# SparkFun_FreeSoC2_V1.net
KiCad netlist of a schematic drawn in EAGLE
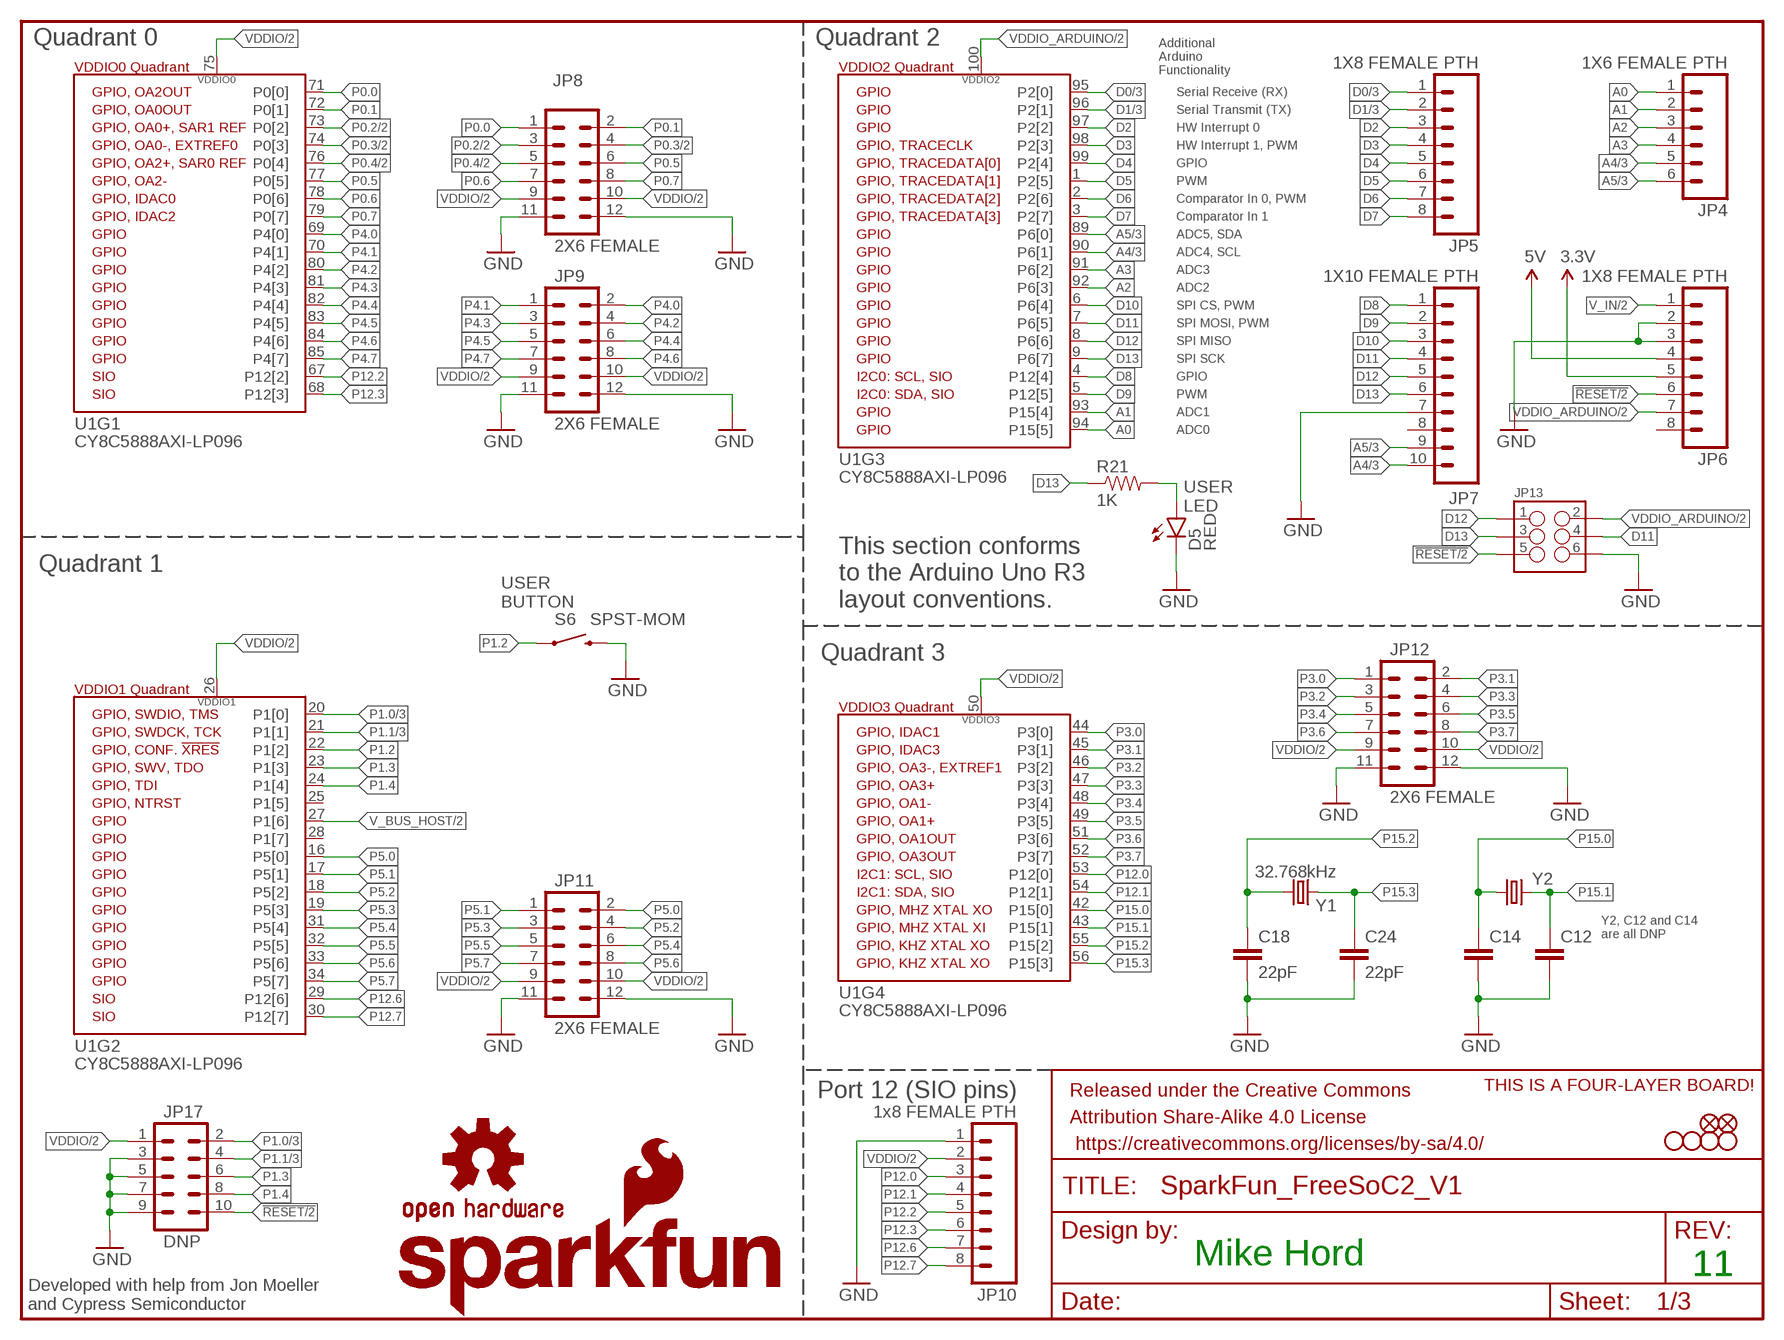
[diagram p0: schematic, sheet 1]
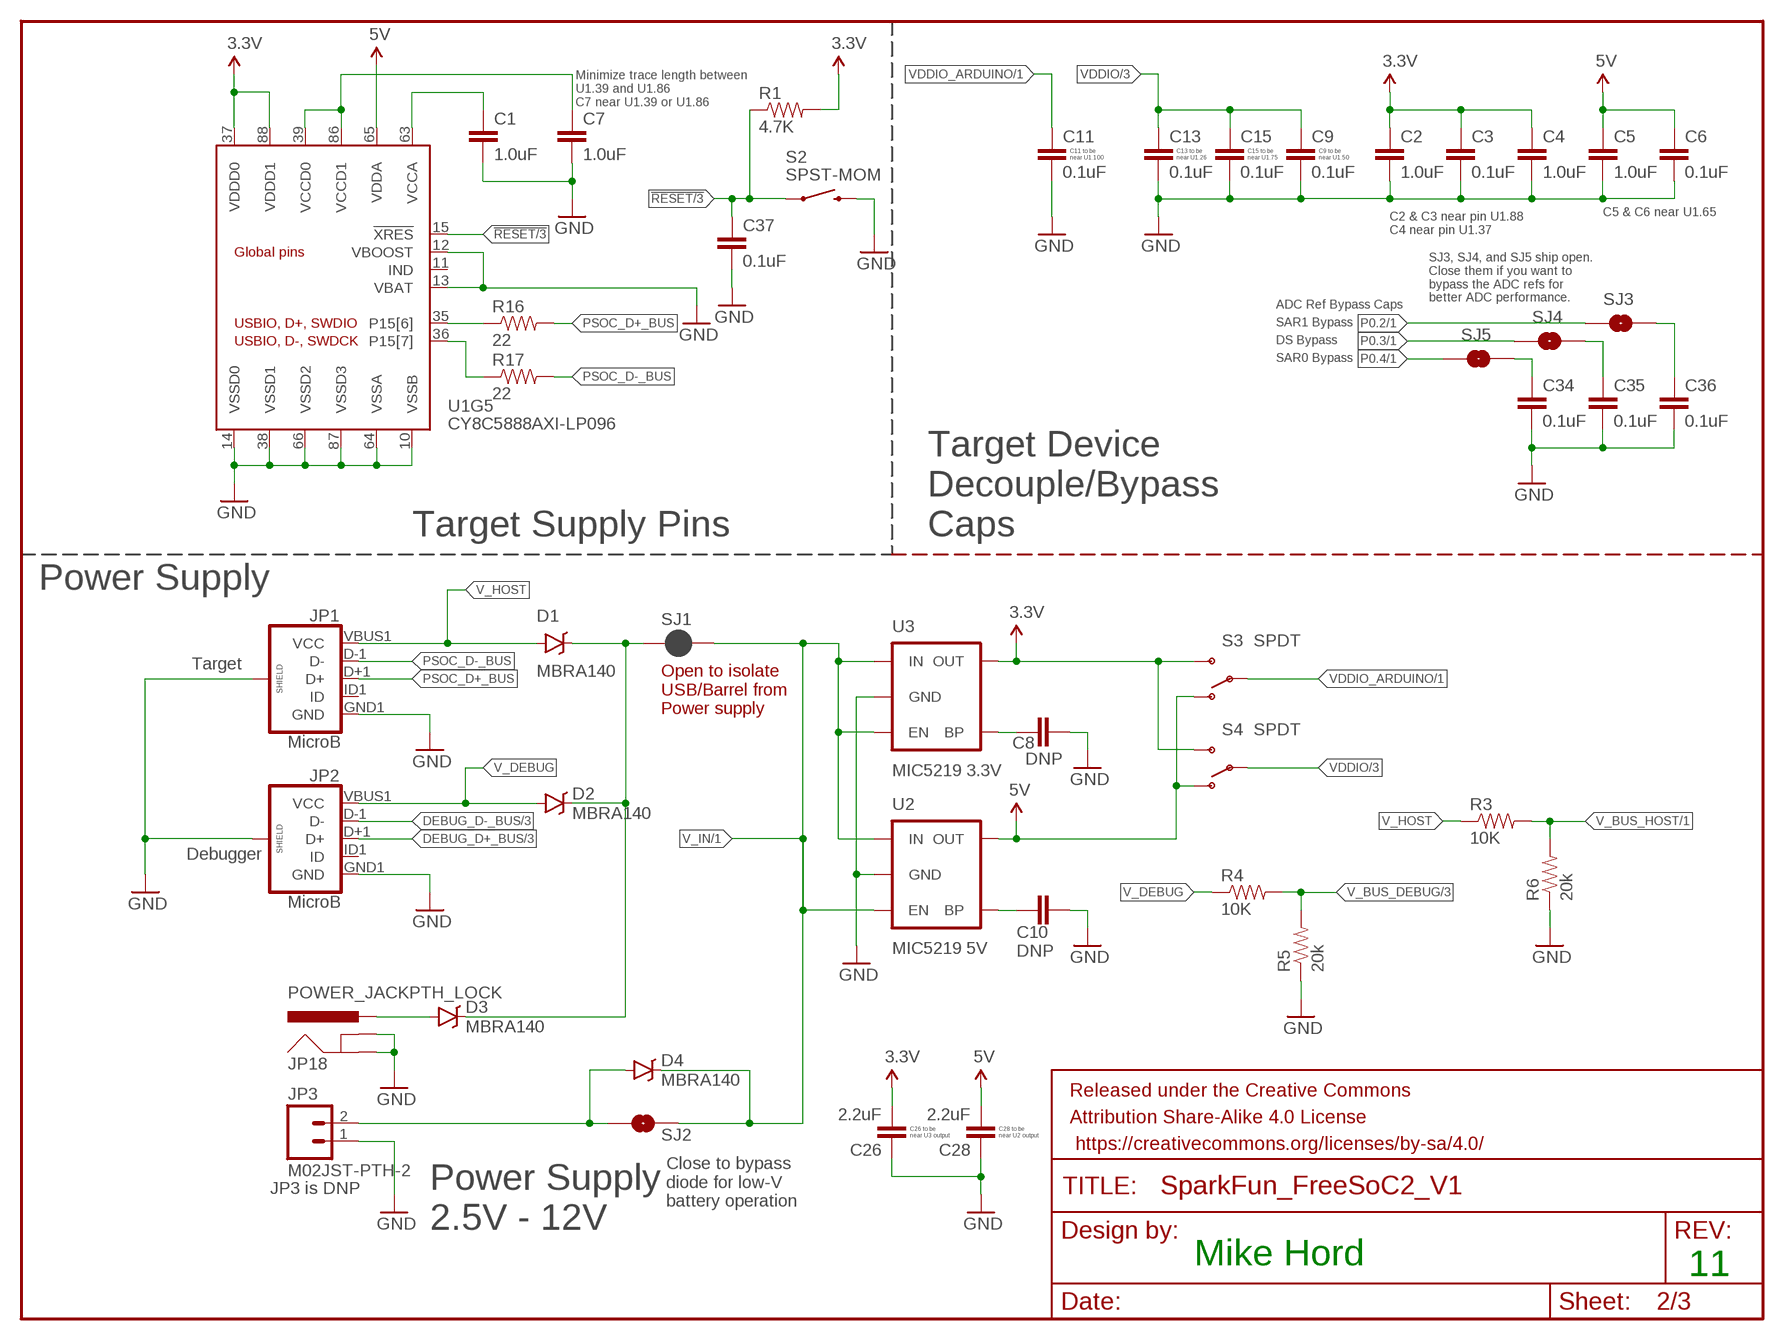
[diagram p1: schematic, sheet 2]
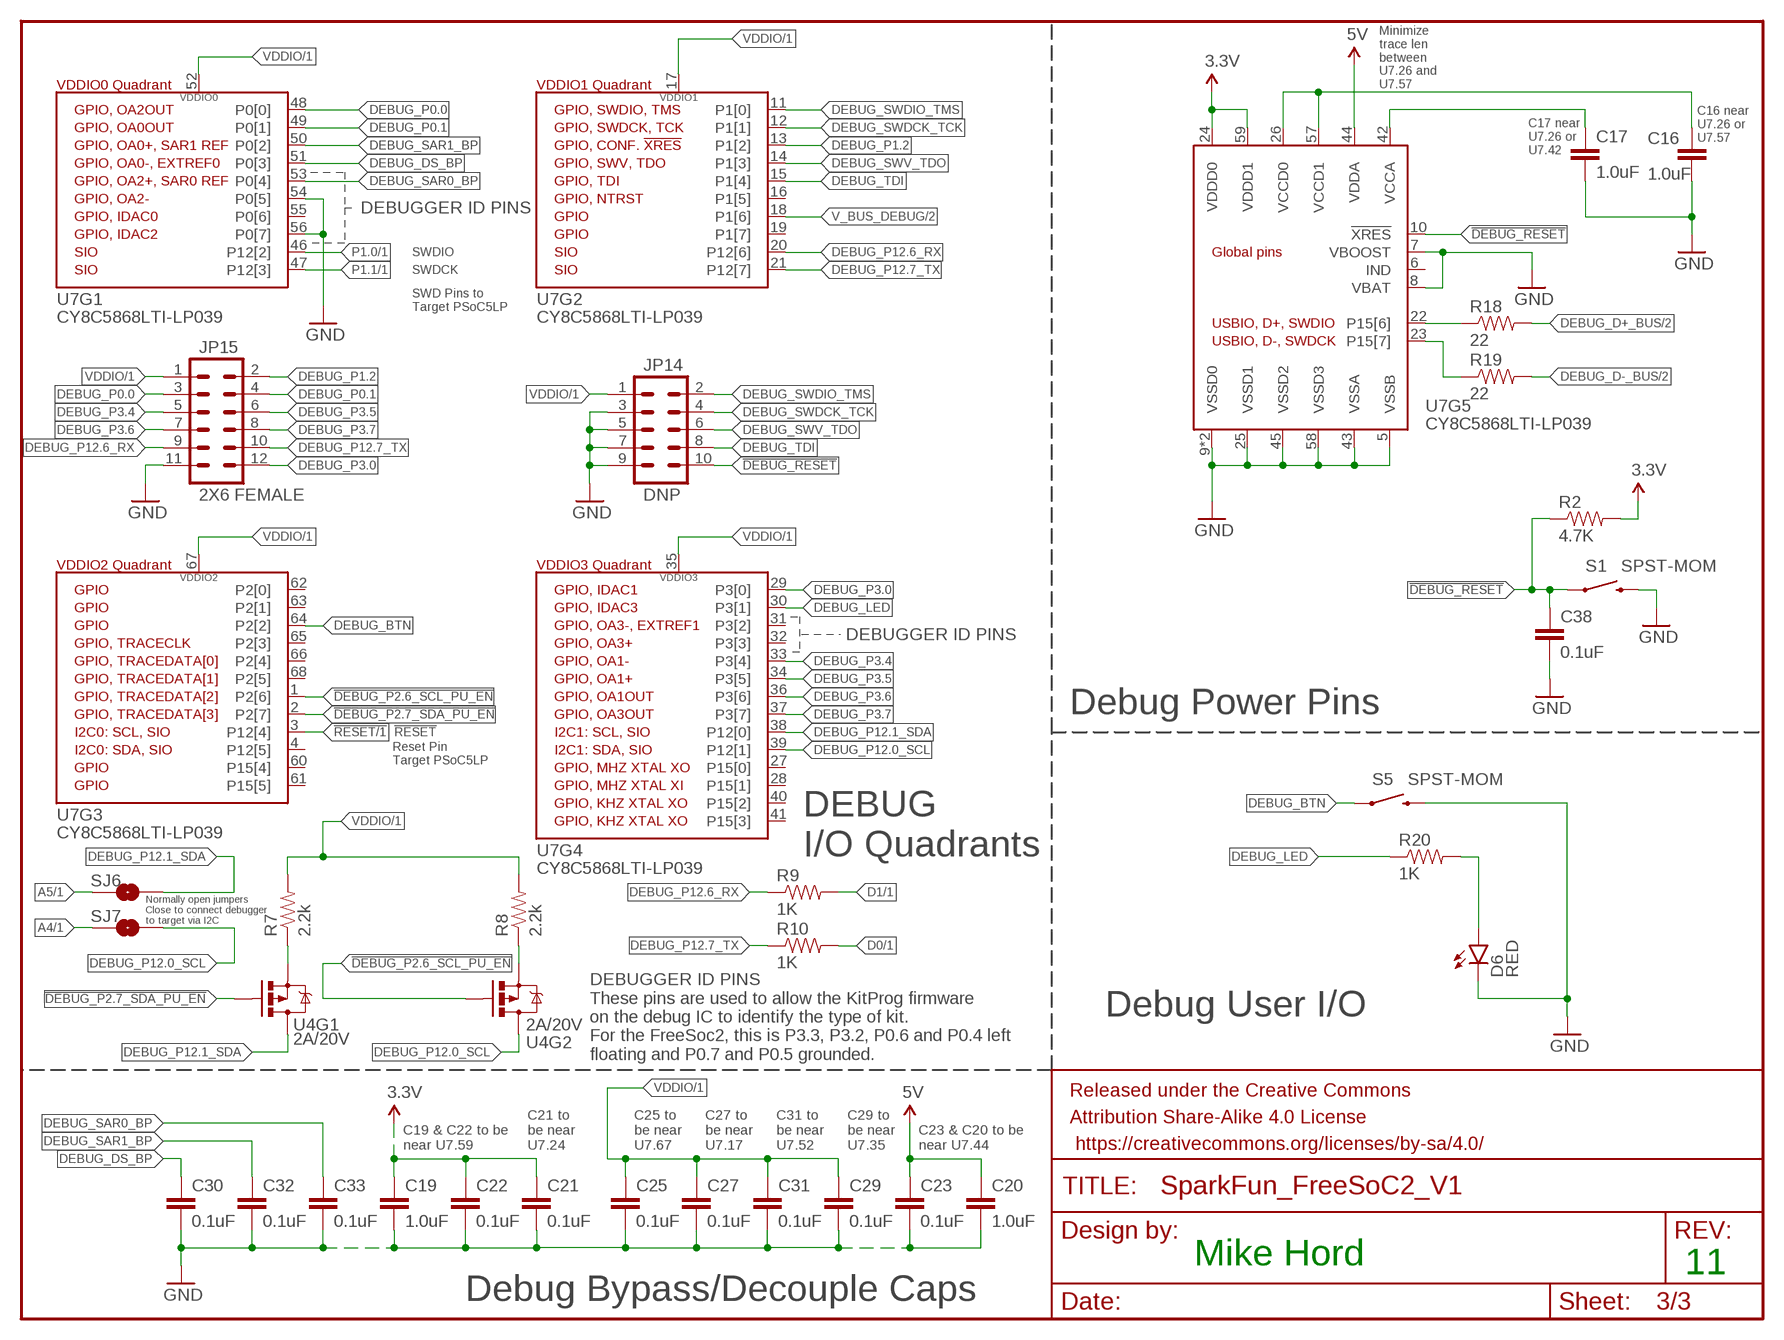
[diagram p2: schematic, sheet 3]

(export (version "E")
  (design (tool "Eeschema 10.0.6"))
  (components
    (comp (ref "C1")
      (value "1.0uF")
      (footprint "eagle-import:0402-CAP")
      (libsource (lib "eagle-import") (part "1.0UF-16V-10%(0402)"))
    )
    (comp (ref "C2")
      (value "1.0uF")
      (footprint "eagle-import:0402-CAP")
      (libsource (lib "eagle-import") (part "1.0UF-16V-10%(0402)"))
    )
    (comp (ref "C3")
      (value "0.1uF")
      (footprint "eagle-import:0402-CAP")
      (libsource (lib "eagle-import") (part "0.1UF-16V(+-10%)(0402)"))
    )
    (comp (ref "C4")
      (value "1.0uF")
      (footprint "eagle-import:0402-CAP")
      (libsource (lib "eagle-import") (part "1.0UF-16V-10%(0402)"))
    )
    (comp (ref "C5")
      (value "1.0uF")
      (footprint "eagle-import:0402-CAP")
      (libsource (lib "eagle-import") (part "1.0UF-16V-10%(0402)"))
    )
    (comp (ref "C6")
      (value "0.1uF")
      (footprint "eagle-import:0402-CAP")
      (libsource (lib "eagle-import") (part "0.1UF-16V(+-10%)(0402)"))
    )
    (comp (ref "C7")
      (value "1.0uF")
      (footprint "eagle-import:0402-CAP")
      (libsource (lib "eagle-import") (part "1.0UF-16V-10%(0402)"))
    )
    (comp (ref "C8")
      (value "DNP")
      (footprint "eagle-import:0603-CAP")
      (libsource (lib "eagle-import") (part "470PF-50V-5%(0603)SMD"))
    )
    (comp (ref "C9")
      (value "0.1uF")
      (footprint "eagle-import:0402-CAP")
      (libsource (lib "eagle-import") (part "0.1UF-16V(+-10%)(0402)"))
    )
    (comp (ref "C10")
      (value "DNP")
      (footprint "eagle-import:0603-CAP")
      (libsource (lib "eagle-import") (part "470PF-50V-5%(0603)SMD"))
    )
    (comp (ref "C11")
      (value "0.1uF")
      (footprint "eagle-import:0402-CAP")
      (libsource (lib "eagle-import") (part "0.1UF-16V(+-10%)(0402)"))
    )
    (comp (ref "C13")
      (value "0.1uF")
      (footprint "eagle-import:0402-CAP")
      (libsource (lib "eagle-import") (part "0.1UF-16V(+-10%)(0402)"))
    )
    (comp (ref "C15")
      (value "0.1uF")
      (footprint "eagle-import:0402-CAP")
      (libsource (lib "eagle-import") (part "0.1UF-16V(+-10%)(0402)"))
    )
    (comp (ref "C26")
      (value "2.2uF")
      (footprint "eagle-import:0603-CAP")
      (libsource (lib "eagle-import") (part "2.2UF-10V-20%(0603)"))
    )
    (comp (ref "C28")
      (value "2.2uF")
      (footprint "eagle-import:0603-CAP")
      (libsource (lib "eagle-import") (part "2.2UF-10V-20%(0603)"))
    )
    (comp (ref "C34")
      (value "0.1uF")
      (footprint "eagle-import:0402-CAP")
      (libsource (lib "eagle-import") (part "0.1UF-16V(+-10%)(0402)"))
    )
    (comp (ref "C35")
      (value "0.1uF")
      (footprint "eagle-import:0402-CAP")
      (libsource (lib "eagle-import") (part "0.1UF-16V(+-10%)(0402)"))
    )
    (comp (ref "C36")
      (value "0.1uF")
      (footprint "eagle-import:0402-CAP")
      (libsource (lib "eagle-import") (part "0.1UF-16V(+-10%)(0402)"))
    )
    (comp (ref "C37")
      (value "0.1uF")
      (footprint "eagle-import:0402-CAP")
      (libsource (lib "eagle-import") (part "0.1UF-16V(+-10%)(0402)"))
    )
    (comp (ref "D1")
      (value "MBRA140")
      (footprint "eagle-import:SMA-DIODE")
      (libsource (lib "eagle-import") (part "MBRA140"))
    )
    (comp (ref "D2")
      (value "MBRA140")
      (footprint "eagle-import:SMA-DIODE")
      (libsource (lib "eagle-import") (part "MBRA140"))
    )
    (comp (ref "D3")
      (value "MBRA140")
      (footprint "eagle-import:SMA-DIODE")
      (libsource (lib "eagle-import") (part "MBRA140"))
    )
    (comp (ref "D4")
      (value "MBRA140")
      (footprint "eagle-import:SMA-DIODE")
      (libsource (lib "eagle-import") (part "MBRA140"))
    )
    (comp (ref "FRAME2")
      (value "FRAME-LETTERNO_PACKAGE")
      (footprint "eagle-import:DUMMY")
      (fields (field (name "DESIGNER") "Nobody"))
      (libsource (lib "eagle-import") (part "FRAME-LETTERNO_PACKAGE"))
    )
    (comp (ref "JP1")
      (value "MicroB")
      (footprint "eagle-import:USB-B-MICRO-SMD_V03")
      (libsource (lib "eagle-import") (part "USB_MICROB_PLUGCONN-11752"))
    )
    (comp (ref "JP2")
      (value "MicroB")
      (footprint "eagle-import:USB-B-MICRO-SMD_V03")
      (libsource (lib "eagle-import") (part "USB_MICROB_PLUGCONN-11752"))
    )
    (comp (ref "JP3")
      (value "M02JST-PTH-2")
      (footprint "eagle-import:JST-2-PTH")
      (libsource (lib "eagle-import") (part "M02JST-PTH-2"))
    )
    (comp (ref "JP18")
      (value "POWER_JACKPTH_LOCK")
      (footprint "eagle-import:POWER_JACK_PTH_LOCK")
      (libsource (lib "eagle-import") (part "POWER_JACKPTH_LOCK"))
    )
    (comp (ref "R1")
      (value "4.7K")
      (footprint "eagle-import:0603-RES")
      (libsource (lib "eagle-import") (part "4.7KOHM-1/10W-1%(0603)"))
    )
    (comp (ref "R3")
      (value "10K")
      (footprint "eagle-import:0603-RES")
      (libsource (lib "eagle-import") (part "10KOHM-1/10W-1%(0603)0603"))
    )
    (comp (ref "R4")
      (value "10K")
      (footprint "eagle-import:0603-RES")
      (libsource (lib "eagle-import") (part "10KOHM-1/10W-1%(0603)0603"))
    )
    (comp (ref "R5")
      (value "20k")
      (footprint "eagle-import:0603-RES")
      (libsource (lib "eagle-import") (part "20KOHM1/10W1%(0603)"))
    )
    (comp (ref "R6")
      (value "20k")
      (footprint "eagle-import:0603-RES")
      (libsource (lib "eagle-import") (part "20KOHM1/10W1%(0603)"))
    )
    (comp (ref "R16")
      (value "22")
      (footprint "eagle-import:0402-RES")
      (libsource (lib "eagle-import") (part "22OHM1/10W1%(0402)"))
    )
    (comp (ref "R17")
      (value "22")
      (footprint "eagle-import:0402-RES")
      (libsource (lib "eagle-import") (part "22OHM1/10W1%(0402)"))
    )
    (comp (ref "S2")
      (value "SPST-MOM")
      (footprint "eagle-import:TACTILE-SWITCH-SMD")
      (libsource (lib "eagle-import") (part "SWITCH-MOMENTARY-2SMD"))
    )
    (comp (ref "S3")
      (value "SPDT")
      (footprint "eagle-import:SWITCH-SPDT_LOCK.007S")
      (libsource (lib "eagle-import") (part "SWITCH-SPDTPTH_LOCK"))
    )
    (comp (ref "S4")
      (value "SPDT")
      (footprint "eagle-import:SWITCH-SPDT_LOCK.007S")
      (libsource (lib "eagle-import") (part "SWITCH-SPDTPTH_LOCK"))
    )
    (comp (ref "SJ1")
      (value "JUMPER-PAD-2-NC_BY_PASTE")
      (footprint "eagle-import:PAD-JUMPER-2-NC_BY_PASTE_YES_SILK")
      (libsource (lib "eagle-import") (part "JUMPER-PAD-2-NC_BY_PASTE"))
    )
    (comp (ref "SJ2")
      (value "JUMPER-PAD-2-NOYES_SILK")
      (footprint "eagle-import:PAD-JUMPER-2-NO_YES_SILK")
      (libsource (lib "eagle-import") (part "JUMPER-PAD-2-NOYES_SILK"))
    )
    (comp (ref "SJ3")
      (value "JUMPER-PAD-2-NO")
      (footprint "eagle-import:PAD-JUMPER-2-NO_NO_SILK")
      (libsource (lib "eagle-import") (part "JUMPER-PAD-2-NO"))
    )
    (comp (ref "SJ4")
      (value "JUMPER-PAD-2-NO")
      (footprint "eagle-import:PAD-JUMPER-2-NO_NO_SILK")
      (libsource (lib "eagle-import") (part "JUMPER-PAD-2-NO"))
    )
    (comp (ref "SJ5")
      (value "JUMPER-PAD-2-NO")
      (footprint "eagle-import:PAD-JUMPER-2-NO_NO_SILK")
      (libsource (lib "eagle-import") (part "JUMPER-PAD-2-NO"))
    )
    (comp (ref "U1")
      (value "CY8C5888AXI-LP096")
      (footprint "eagle-import:TQFP-100-14X14MM")
      (libsource (lib "eagle-import") (part "PSOC_5LP_100QFP"))
    )
    (comp (ref "U2")
      (value "MIC5219 5V")
      (footprint "eagle-import:SOT23-5")
      (libsource (lib "eagle-import") (part "V_REG_MIC52195V"))
    )
    (comp (ref "U3")
      (value "MIC5219 3.3V")
      (footprint "eagle-import:SOT23-5")
      (libsource (lib "eagle-import") (part "V_REG_MIC52193.3V"))
    )
    (comp (ref "C16")
      (value "1.0uF")
      (footprint "eagle-import:0402-CAP")
      (libsource (lib "eagle-import") (part "1.0UF-16V-10%(0402)"))
    )
    (comp (ref "C17")
      (value "1.0uF")
      (footprint "eagle-import:0402-CAP")
      (libsource (lib "eagle-import") (part "1.0UF-16V-10%(0402)"))
    )
    (comp (ref "C19")
      (value "1.0uF")
      (footprint "eagle-import:0402-CAP")
      (libsource (lib "eagle-import") (part "1.0UF-16V-10%(0402)"))
    )
    (comp (ref "C20")
      (value "1.0uF")
      (footprint "eagle-import:0402-CAP")
      (libsource (lib "eagle-import") (part "1.0UF-16V-10%(0402)"))
    )
    (comp (ref "C21")
      (value "0.1uF")
      (footprint "eagle-import:0402-CAP")
      (libsource (lib "eagle-import") (part "0.1UF-16V(+-10%)(0402)"))
    )
    (comp (ref "C22")
      (value "0.1uF")
      (footprint "eagle-import:0402-CAP")
      (libsource (lib "eagle-import") (part "0.1UF-16V(+-10%)(0402)"))
    )
    (comp (ref "C23")
      (value "0.1uF")
      (footprint "eagle-import:0402-CAP")
      (libsource (lib "eagle-import") (part "0.1UF-16V(+-10%)(0402)"))
    )
    (comp (ref "C25")
      (value "0.1uF")
      (footprint "eagle-import:0402-CAP")
      (libsource (lib "eagle-import") (part "0.1UF-16V(+-10%)(0402)"))
    )
    (comp (ref "C27")
      (value "0.1uF")
      (footprint "eagle-import:0402-CAP")
      (libsource (lib "eagle-import") (part "0.1UF-16V(+-10%)(0402)"))
    )
    (comp (ref "C29")
      (value "0.1uF")
      (footprint "eagle-import:0402-CAP")
      (libsource (lib "eagle-import") (part "0.1UF-16V(+-10%)(0402)"))
    )
    (comp (ref "C30")
      (value "0.1uF")
      (footprint "eagle-import:0402-CAP")
      (libsource (lib "eagle-import") (part "0.1UF-16V(+-10%)(0402)"))
    )
    (comp (ref "C31")
      (value "0.1uF")
      (footprint "eagle-import:0402-CAP")
      (libsource (lib "eagle-import") (part "0.1UF-16V(+-10%)(0402)"))
    )
    (comp (ref "C32")
      (value "0.1uF")
      (footprint "eagle-import:0402-CAP")
      (libsource (lib "eagle-import") (part "0.1UF-16V(+-10%)(0402)"))
    )
    (comp (ref "C33")
      (value "0.1uF")
      (footprint "eagle-import:0402-CAP")
      (libsource (lib "eagle-import") (part "0.1UF-16V(+-10%)(0402)"))
    )
    (comp (ref "C38")
      (value "0.1uF")
      (footprint "eagle-import:0402-CAP")
      (libsource (lib "eagle-import") (part "0.1UF-16V(+-10%)(0402)"))
    )
    (comp (ref "D6")
      (value "RED")
      (footprint "eagle-import:LED-0603")
      (libsource (lib "eagle-import") (part "LED-RED0603"))
    )
    (comp (ref "FRAME1")
      (value "FRAME-LETTERNO_PACKAGE")
      (footprint "eagle-import:DUMMY")
      (fields (field (name "DESIGNER") "Nobody"))
      (libsource (lib "eagle-import") (part "FRAME-LETTERNO_PACKAGE"))
    )
    (comp (ref "JP14")
      (value "DNP")
      (footprint "eagle-import:2X5_PTH_SILK_.05")
      (libsource (lib "eagle-import") (part "M05X20.05_IN_PTH_SILK"))
    )
    (comp (ref "JP15")
      (value "2X6 FEMALE")
      (footprint "eagle-import:2X6")
      (libsource (lib "eagle-import") (part "M06X2PTH_FEMALE"))
    )
    (comp (ref "R2")
      (value "4.7K")
      (footprint "eagle-import:0603-RES")
      (libsource (lib "eagle-import") (part "4.7KOHM-1/10W-1%(0603)"))
    )
    (comp (ref "R7")
      (value "2.2k")
      (footprint "eagle-import:0603-RES")
      (libsource (lib "eagle-import") (part "2.2KOHM-1/10W-1%(0603)"))
    )
    (comp (ref "R8")
      (value "2.2k")
      (footprint "eagle-import:0603-RES")
      (libsource (lib "eagle-import") (part "2.2KOHM-1/10W-1%(0603)"))
    )
    (comp (ref "R9")
      (value "1K")
      (footprint "eagle-import:0603-RES")
      (libsource (lib "eagle-import") (part "1KOHM1/10W1%(0603)"))
    )
    (comp (ref "R10")
      (value "1K")
      (footprint "eagle-import:0603-RES")
      (libsource (lib "eagle-import") (part "1KOHM1/10W1%(0603)"))
    )
    (comp (ref "R18")
      (value "22")
      (footprint "eagle-import:0402-RES")
      (libsource (lib "eagle-import") (part "22OHM1/10W1%(0402)"))
    )
    (comp (ref "R19")
      (value "22")
      (footprint "eagle-import:0402-RES")
      (libsource (lib "eagle-import") (part "22OHM1/10W1%(0402)"))
    )
    (comp (ref "R20")
      (value "1K")
      (footprint "eagle-import:0603-RES")
      (libsource (lib "eagle-import") (part "1KOHM1/10W1%(0603)"))
    )
    (comp (ref "S1")
      (value "SPST-MOM")
      (footprint "eagle-import:TACTILE-SWITCH-SMD")
      (libsource (lib "eagle-import") (part "SWITCH-MOMENTARY-2SMD"))
    )
    (comp (ref "S5")
      (value "SPST-MOM")
      (footprint "eagle-import:TACTILE-SWITCH-SMD")
      (libsource (lib "eagle-import") (part "SWITCH-MOMENTARY-2SMD"))
    )
    (comp (ref "SJ6")
      (value "JUMPER-PAD-2-NO")
      (footprint "eagle-import:PAD-JUMPER-2-NO_NO_SILK")
      (libsource (lib "eagle-import") (part "JUMPER-PAD-2-NO"))
    )
    (comp (ref "SJ7")
      (value "JUMPER-PAD-2-NO")
      (footprint "eagle-import:PAD-JUMPER-2-NO_NO_SILK")
      (libsource (lib "eagle-import") (part "JUMPER-PAD-2-NO"))
    )
    (comp (ref "U4")
      (value "2A/20V")
      (footprint "eagle-import:SOT26")
      (libsource (lib "eagle-import") (part "MOSFET-PCHANNEL_DUALSOT26"))
    )
    (comp (ref "U7")
      (value "CY8C5868LTI-LP039")
      (footprint "eagle-import:QFN-68")
      (libsource (lib "eagle-import") (part "PSOC_5LP_68QFN"))
    )
    (comp (ref "C12")
      (value "CAPPTH")
      (footprint "eagle-import:CAP-PTH-SMALL")
      (libsource (lib "eagle-import") (part "CAPPTH"))
    )
    (comp (ref "C14")
      (value "CAPPTH")
      (footprint "eagle-import:CAP-PTH-SMALL")
      (libsource (lib "eagle-import") (part "CAPPTH"))
    )
    (comp (ref "C18")
      (value "22pF")
      (footprint "eagle-import:0603-CAP")
      (libsource (lib "eagle-import") (part "22PF-50V-5%(0603)"))
    )
    (comp (ref "C24")
      (value "22pF")
      (footprint "eagle-import:0603-CAP")
      (libsource (lib "eagle-import") (part "22PF-50V-5%(0603)"))
    )
    (comp (ref "D5")
      (value "RED")
      (footprint "eagle-import:LED-0603")
      (libsource (lib "eagle-import") (part "LED-RED0603"))
    )
    (comp (ref "FID1")
      (value "FIDUCIAL1X2")
      (footprint "eagle-import:FIDUCIAL-1X2")
      (libsource (lib "eagle-import") (part "FIDUCIAL1X2"))
    )
    (comp (ref "FID2")
      (value "FIDUCIAL1X2")
      (footprint "eagle-import:FIDUCIAL-1X2")
      (libsource (lib "eagle-import") (part "FIDUCIAL1X2"))
    )
    (comp (ref "FRAME3")
      (value "FRAME-LETTERNO_PACKAGE")
      (footprint "eagle-import:DUMMY")
      (fields (field (name "DESIGNER") "Nobody"))
      (libsource (lib "eagle-import") (part "FRAME-LETTERNO_PACKAGE"))
    )
    (comp (ref "JP4")
      (value "1X6 FEMALE PTH")
      (footprint "eagle-import:1X06-SIP_LOCK")
      (libsource (lib "eagle-import") (part "M06SIP_LOCK"))
    )
    (comp (ref "JP5")
      (value "1X8 FEMALE PTH")
      (footprint "eagle-import:1X08_LOCK")
      (libsource (lib "eagle-import") (part "M08LOCK"))
    )
    (comp (ref "JP6")
      (value "1X8 FEMALE PTH")
      (footprint "eagle-import:1X08_LOCK")
      (libsource (lib "eagle-import") (part "M08LOCK"))
    )
    (comp (ref "JP7")
      (value "1X10 FEMALE PTH")
      (footprint "eagle-import:1X10_LOCK")
      (libsource (lib "eagle-import") (part "M10LOCK"))
    )
    (comp (ref "JP8")
      (value "2X6 FEMALE")
      (footprint "eagle-import:2X6")
      (libsource (lib "eagle-import") (part "M06X2PTH_FEMALE"))
    )
    (comp (ref "JP9")
      (value "2X6 FEMALE")
      (footprint "eagle-import:2X6")
      (libsource (lib "eagle-import") (part "M06X2PTH_FEMALE"))
    )
    (comp (ref "JP10")
      (value "1x8 FEMALE PTH")
      (footprint "eagle-import:1X08_LOCK")
      (libsource (lib "eagle-import") (part "M08LOCK"))
    )
    (comp (ref "JP11")
      (value "2X6 FEMALE")
      (footprint "eagle-import:2X6")
      (libsource (lib "eagle-import") (part "M06X2PTH_FEMALE"))
    )
    (comp (ref "JP12")
      (value "2X6 FEMALE")
      (footprint "eagle-import:2X6")
      (libsource (lib "eagle-import") (part "M06X2PTH_FEMALE"))
    )
    (comp (ref "JP13")
      (value "M03X22X3_SILK_MALE_PTH")
      (footprint "eagle-import:2X3")
      (libsource (lib "eagle-import") (part "M03X22X3_SILK_MALE_PTH"))
    )
    (comp (ref "JP17")
      (value "DNP")
      (footprint "eagle-import:2X5_PTH_SILK_.05")
      (libsource (lib "eagle-import") (part "M05X20.05_IN_PTH_SILK"))
    )
    (comp (ref "LOGO1")
      (value "SFE_LOGO_NAME_FLAME.2_INCH")
      (footprint "eagle-import:SFE_LOGO_NAME_FLAME_.2")
      (libsource (lib "eagle-import") (part "SFE_LOGO_NAME_FLAME.2_INCH"))
    )
    (comp (ref "LOGO2")
      (value "OSHW-LOGOS")
      (footprint "eagle-import:OSHW-LOGO-S")
      (libsource (lib "eagle-import") (part "OSHW-LOGOS"))
    )
    (comp (ref "R21")
      (value "1K")
      (footprint "eagle-import:0603-RES")
      (libsource (lib "eagle-import") (part "1KOHM1/10W1%(0603)"))
    )
    (comp (ref "S6")
      (value "SPST-MOM")
      (footprint "eagle-import:TACTILE-SWITCH-SMD")
      (libsource (lib "eagle-import") (part "SWITCH-MOMENTARY-2SMD"))
    )
    (comp (ref "STANDOFF1")
      (value "STAND-OFF")
      (footprint "eagle-import:STAND-OFF")
      (libsource (lib "eagle-import") (part "STAND-OFF"))
    )
    (comp (ref "STANDOFF2")
      (value "STAND-OFF")
      (footprint "eagle-import:STAND-OFF")
      (libsource (lib "eagle-import") (part "STAND-OFF"))
    )
    (comp (ref "STANDOFF3")
      (value "STAND-OFF")
      (footprint "eagle-import:STAND-OFF")
      (libsource (lib "eagle-import") (part "STAND-OFF"))
    )
    (comp (ref "STANDOFF4")
      (value "STAND-OFF")
      (footprint "eagle-import:STAND-OFF")
      (libsource (lib "eagle-import") (part "STAND-OFF"))
    )
    (comp (ref "U$1")
      (value "FOUR_LAYER_WARNING")
      (footprint "eagle-import:FOUR_LAYER_WARNING")
      (libsource (lib "eagle-import") (part "FOUR_LAYER_WARNING"))
    )
    (comp (ref "Y1")
      (value "32.768kHz")
      (footprint "eagle-import:TC26H")
      (libsource (lib "eagle-import") (part "CRYSTALTC26H"))
    )
    (comp (ref "Y2")
      (value "CRYSTALHC49US")
      (footprint "eagle-import:HC49US")
      (libsource (lib "eagle-import") (part "CRYSTALHC49US"))
    )
  )
  (nets
    (net (code "1") (name "3.3V") (class "Default")
      (node (ref "C19") (pin "1") (pinfunction "1_1") (pintype "passive"))
      (node (ref "C2") (pin "1") (pinfunction "1_1") (pintype "passive"))
      (node (ref "C21") (pin "1") (pinfunction "1_1") (pintype "passive"))
      (node (ref "C22") (pin "1") (pinfunction "1_1") (pintype "passive"))
      (node (ref "C26") (pin "2") (pinfunction "2_2") (pintype "passive"))
      (node (ref "C3") (pin "1") (pinfunction "1_1") (pintype "passive"))
      (node (ref "C4") (pin "1") (pinfunction "1_1") (pintype "passive"))
      (node (ref "JP6") (pin "5") (pinfunction "5_5") (pintype "passive"))
      (node (ref "R1") (pin "2") (pinfunction "2_2") (pintype "passive"))
      (node (ref "R2") (pin "2") (pinfunction "2_2") (pintype "passive"))
      (node (ref "S3") (pin "3") (pinfunction "S_3") (pintype "passive"))
      (node (ref "S4") (pin "3") (pinfunction "S_3") (pintype "passive"))
      (node (ref "U1") (pin "37") (pinfunction "VDDD0_37") (pintype "bidirectional"))
      (node (ref "U1") (pin "88") (pinfunction "VDDD1_88") (pintype "bidirectional"))
      (node (ref "U3") (pin "5") (pinfunction "OUT_5") (pintype "passive"))
      (node (ref "U7") (pin "24") (pinfunction "VDDD0_24") (pintype "bidirectional"))
      (node (ref "U7") (pin "59") (pinfunction "VDDD1_59") (pintype "bidirectional"))
    )
    (net (code "2") (name "5V") (class "Default")
      (node (ref "C20") (pin "1") (pinfunction "1_1") (pintype "passive"))
      (node (ref "C23") (pin "1") (pinfunction "1_1") (pintype "passive"))
      (node (ref "C28") (pin "2") (pinfunction "2_2") (pintype "passive"))
      (node (ref "C5") (pin "1") (pinfunction "1_1") (pintype "passive"))
      (node (ref "C6") (pin "1") (pinfunction "1_1") (pintype "passive"))
      (node (ref "JP6") (pin "4") (pinfunction "4_4") (pintype "passive"))
      (node (ref "S3") (pin "1") (pinfunction "O_1") (pintype "passive"))
      (node (ref "S4") (pin "1") (pinfunction "O_1") (pintype "passive"))
      (node (ref "U1") (pin "65") (pinfunction "VDDA_65") (pintype "bidirectional"))
      (node (ref "U2") (pin "5") (pinfunction "OUT_5") (pintype "passive"))
      (node (ref "U7") (pin "44") (pinfunction "VDDA_44") (pintype "bidirectional"))
    )
    (net (code "3") (name "A0") (class "Default")
      (node (ref "JP4") (pin "1") (pinfunction "1_1") (pintype "passive"))
      (node (ref "U1") (pin "94") (pinfunction "P15[5]_94") (pintype "bidirectional"))
    )
    (net (code "4") (name "A1") (class "Default")
      (node (ref "JP4") (pin "2") (pinfunction "2_2") (pintype "passive"))
      (node (ref "U1") (pin "93") (pinfunction "P15[4]_93") (pintype "bidirectional"))
    )
    (net (code "5") (name "A2") (class "Default")
      (node (ref "JP4") (pin "3") (pinfunction "3_3") (pintype "passive"))
      (node (ref "U1") (pin "92") (pinfunction "P6[3]_92") (pintype "bidirectional"))
    )
    (net (code "6") (name "A3") (class "Default")
      (node (ref "JP4") (pin "4") (pinfunction "4_4") (pintype "passive"))
      (node (ref "U1") (pin "91") (pinfunction "P6[2]_91") (pintype "bidirectional"))
    )
    (net (code "7") (name "A4") (class "Default")
      (node (ref "JP4") (pin "5") (pinfunction "5_5") (pintype "passive"))
      (node (ref "JP7") (pin "10") (pinfunction "10_10") (pintype "passive"))
      (node (ref "SJ7") (pin "1") (pinfunction "1_1") (pintype "passive"))
      (node (ref "U1") (pin "90") (pinfunction "P6[1]_90") (pintype "bidirectional"))
    )
    (net (code "8") (name "A5") (class "Default")
      (node (ref "JP4") (pin "6") (pinfunction "6_6") (pintype "passive"))
      (node (ref "JP7") (pin "9") (pinfunction "9_9") (pintype "passive"))
      (node (ref "SJ6") (pin "1") (pinfunction "1_1") (pintype "passive"))
      (node (ref "U1") (pin "89") (pinfunction "P6[0]_89") (pintype "bidirectional"))
    )
    (net (code "9") (name "D0") (class "Default")
      (node (ref "JP5") (pin "1") (pinfunction "1_1") (pintype "passive"))
      (node (ref "R10") (pin "2") (pinfunction "2_2") (pintype "passive"))
      (node (ref "U1") (pin "95") (pinfunction "P2[0]_95") (pintype "bidirectional"))
    )
    (net (code "10") (name "D1") (class "Default")
      (node (ref "JP5") (pin "2") (pinfunction "2_2") (pintype "passive"))
      (node (ref "R9") (pin "2") (pinfunction "2_2") (pintype "passive"))
      (node (ref "U1") (pin "96") (pinfunction "P2[1]_96") (pintype "bidirectional"))
    )
    (net (code "11") (name "D2") (class "Default")
      (node (ref "JP5") (pin "3") (pinfunction "3_3") (pintype "passive"))
      (node (ref "U1") (pin "97") (pinfunction "P2[2]_97") (pintype "bidirectional"))
    )
    (net (code "12") (name "D3") (class "Default")
      (node (ref "JP5") (pin "4") (pinfunction "4_4") (pintype "passive"))
      (node (ref "U1") (pin "98") (pinfunction "P2[3]_98") (pintype "bidirectional"))
    )
    (net (code "13") (name "D4") (class "Default")
      (node (ref "JP5") (pin "5") (pinfunction "5_5") (pintype "passive"))
      (node (ref "U1") (pin "99") (pinfunction "P2[4]_99") (pintype "bidirectional"))
    )
    (net (code "14") (name "D5") (class "Default")
      (node (ref "JP5") (pin "6") (pinfunction "6_6") (pintype "passive"))
      (node (ref "U1") (pin "1") (pinfunction "P2[5]_1") (pintype "bidirectional"))
    )
    (net (code "15") (name "D6") (class "Default")
      (node (ref "JP5") (pin "7") (pinfunction "7_7") (pintype "passive"))
      (node (ref "U1") (pin "2") (pinfunction "P2[6]_2") (pintype "bidirectional"))
    )
    (net (code "16") (name "D7") (class "Default")
      (node (ref "JP5") (pin "8") (pinfunction "8_8") (pintype "passive"))
      (node (ref "U1") (pin "3") (pinfunction "P2[7]_3") (pintype "bidirectional"))
    )
    (net (code "17") (name "D8") (class "Default")
      (node (ref "JP7") (pin "1") (pinfunction "1_1") (pintype "passive"))
      (node (ref "U1") (pin "4") (pinfunction "P12[4]_4") (pintype "bidirectional"))
    )
    (net (code "18") (name "D9") (class "Default")
      (node (ref "JP7") (pin "2") (pinfunction "2_2") (pintype "passive"))
      (node (ref "U1") (pin "5") (pinfunction "P12[5]_5") (pintype "bidirectional"))
    )
    (net (code "19") (name "D10") (class "Default")
      (node (ref "JP7") (pin "3") (pinfunction "3_3") (pintype "passive"))
      (node (ref "U1") (pin "6") (pinfunction "P6[4]_6") (pintype "bidirectional"))
    )
    (net (code "20") (name "D11") (class "Default")
      (node (ref "JP13") (pin "4") (pinfunction "4_4") (pintype "bidirectional"))
      (node (ref "JP7") (pin "4") (pinfunction "4_4") (pintype "passive"))
      (node (ref "U1") (pin "7") (pinfunction "P6[5]_7") (pintype "bidirectional"))
    )
    (net (code "21") (name "D12") (class "Default")
      (node (ref "JP13") (pin "1") (pinfunction "1_1") (pintype "bidirectional"))
      (node (ref "JP7") (pin "5") (pinfunction "5_5") (pintype "passive"))
      (node (ref "U1") (pin "8") (pinfunction "P6[6]_8") (pintype "bidirectional"))
    )
    (net (code "22") (name "D13") (class "Default")
      (node (ref "JP13") (pin "3") (pinfunction "3_3") (pintype "bidirectional"))
      (node (ref "JP7") (pin "6") (pinfunction "6_6") (pintype "passive"))
      (node (ref "R21") (pin "1") (pinfunction "1_1") (pintype "passive"))
      (node (ref "U1") (pin "9") (pinfunction "P6[7]_9") (pintype "bidirectional"))
    )
    (net (code "23") (name "DEBUG_BTN") (class "Default")
      (node (ref "S5") (pin "1") (pinfunction "1_1") (pintype "passive"))
      (node (ref "U7") (pin "64") (pinfunction "P2[2]_64") (pintype "bidirectional"))
    )
    (net (code "24") (name "DEBUG_D+_BUS") (class "Default")
      (node (ref "JP2") (pin "D+1") (pinfunction "D+_D+1") (pintype "bidirectional"))
      (node (ref "R18") (pin "2") (pinfunction "2_2") (pintype "passive"))
    )
    (net (code "25") (name "DEBUG_D-_BUS") (class "Default")
      (node (ref "JP2") (pin "D-1") (pinfunction "D-_D-1") (pintype "bidirectional"))
      (node (ref "R19") (pin "2") (pinfunction "2_2") (pintype "passive"))
    )
    (net (code "26") (name "DEBUG_DS_BP") (class "Default")
      (node (ref "C30") (pin "1") (pinfunction "1_1") (pintype "passive"))
      (node (ref "U7") (pin "51") (pinfunction "P0[3]_51") (pintype "bidirectional"))
    )
    (net (code "27") (name "DEBUG_LED") (class "Default")
      (node (ref "R20") (pin "1") (pinfunction "1_1") (pintype "passive"))
      (node (ref "U7") (pin "30") (pinfunction "P3[1]_30") (pintype "bidirectional"))
    )
    (net (code "28") (name "DEBUG_P0.0") (class "Default")
      (node (ref "JP15") (pin "3") (pinfunction "3_3") (pintype "passive"))
      (node (ref "U7") (pin "48") (pinfunction "P0[0]_48") (pintype "bidirectional"))
    )
    (net (code "29") (name "DEBUG_P0.1") (class "Default")
      (node (ref "JP15") (pin "4") (pinfunction "4_4") (pintype "passive"))
      (node (ref "U7") (pin "49") (pinfunction "P0[1]_49") (pintype "bidirectional"))
    )
    (net (code "30") (name "DEBUG_P1.2") (class "Default")
      (node (ref "JP15") (pin "2") (pinfunction "2_2") (pintype "passive"))
      (node (ref "U7") (pin "13") (pinfunction "P1[2]_13") (pintype "bidirectional"))
    )
    (net (code "31") (name "DEBUG_P3.0") (class "Default")
      (node (ref "JP15") (pin "12") (pinfunction "12_12") (pintype "passive"))
      (node (ref "U7") (pin "29") (pinfunction "P3[0]_29") (pintype "bidirectional"))
    )
    (net (code "32") (name "DEBUG_P3.4") (class "Default")
      (node (ref "JP15") (pin "5") (pinfunction "5_5") (pintype "passive"))
      (node (ref "U7") (pin "33") (pinfunction "P3[4]_33") (pintype "bidirectional"))
    )
    (net (code "33") (name "DEBUG_P3.5") (class "Default")
      (node (ref "JP15") (pin "6") (pinfunction "6_6") (pintype "passive"))
      (node (ref "U7") (pin "34") (pinfunction "P3[5]_34") (pintype "bidirectional"))
    )
    (net (code "34") (name "DEBUG_P3.6") (class "Default")
      (node (ref "JP15") (pin "7") (pinfunction "7_7") (pintype "passive"))
      (node (ref "U7") (pin "36") (pinfunction "P3[6]_36") (pintype "bidirectional"))
    )
    (net (code "35") (name "DEBUG_P3.7") (class "Default")
      (node (ref "JP15") (pin "8") (pinfunction "8_8") (pintype "passive"))
      (node (ref "U7") (pin "37") (pinfunction "P3[7]_37") (pintype "bidirectional"))
    )
    (net (code "36") (name "DEBUG_P12.0_SCL") (class "Default")
      (node (ref "SJ7") (pin "2") (pinfunction "2_2") (pintype "passive"))
      (node (ref "U4") (pin "D2") (pinfunction "D_D2") (pintype "passive"))
      (node (ref "U7") (pin "39") (pinfunction "P12[1]_39") (pintype "bidirectional"))
    )
    (net (code "37") (name "DEBUG_P12.1_SDA") (class "Default")
      (node (ref "SJ6") (pin "2") (pinfunction "2_2") (pintype "passive"))
      (node (ref "U4") (pin "D1") (pinfunction "D_D1") (pintype "passive"))
      (node (ref "U7") (pin "38") (pinfunction "P12[0]_38") (pintype "bidirectional"))
    )
    (net (code "38") (name "DEBUG_P12.6_RX") (class "Default")
      (node (ref "JP15") (pin "9") (pinfunction "9_9") (pintype "passive"))
      (node (ref "R9") (pin "1") (pinfunction "1_1") (pintype "passive"))
      (node (ref "U7") (pin "20") (pinfunction "P12[6]_20") (pintype "bidirectional"))
    )
    (net (code "39") (name "DEBUG_P12.7_TX") (class "Default")
      (node (ref "JP15") (pin "10") (pinfunction "10_10") (pintype "passive"))
      (node (ref "R10") (pin "1") (pinfunction "1_1") (pintype "passive"))
      (node (ref "U7") (pin "21") (pinfunction "P12[7]_21") (pintype "bidirectional"))
    )
    (net (code "40") (name "DEBUG_SAR0_BP") (class "Default")
      (node (ref "C33") (pin "1") (pinfunction "1_1") (pintype "passive"))
      (node (ref "U7") (pin "53") (pinfunction "P0[4]_53") (pintype "bidirectional"))
    )
    (net (code "41") (name "DEBUG_SAR1_BP") (class "Default")
      (node (ref "C32") (pin "1") (pinfunction "1_1") (pintype "passive"))
      (node (ref "U7") (pin "50") (pinfunction "P0[2]_50") (pintype "bidirectional"))
    )
    (net (code "42") (name "DEBUG_SWDCK_TCK") (class "Default")
      (node (ref "JP14") (pin "4") (pinfunction "4_4") (pintype "passive"))
      (node (ref "U7") (pin "12") (pinfunction "P1[1]_12") (pintype "bidirectional"))
    )
    (net (code "43") (name "DEBUG_SWDIO_TMS") (class "Default")
      (node (ref "JP14") (pin "2") (pinfunction "2_2") (pintype "passive"))
      (node (ref "U7") (pin "11") (pinfunction "P1[0]_11") (pintype "bidirectional"))
    )
    (net (code "44") (name "DEBUG_SWV_TDO") (class "Default")
      (node (ref "JP14") (pin "6") (pinfunction "6_6") (pintype "passive"))
      (node (ref "U7") (pin "14") (pinfunction "P1[3]_14") (pintype "bidirectional"))
    )
    (net (code "45") (name "DEBUG_TDI") (class "Default")
      (node (ref "JP14") (pin "8") (pinfunction "8_8") (pintype "passive"))
      (node (ref "U7") (pin "15") (pinfunction "P1[4]_15") (pintype "bidirectional"))
    )
    (net (code "46") (name "GND") (class "Default")
      (node (ref "C1") (pin "2") (pinfunction "2_2") (pintype "passive"))
      (node (ref "C10") (pin "2") (pinfunction "2_2") (pintype "passive"))
      (node (ref "C11") (pin "2") (pinfunction "2_2") (pintype "passive"))
      (node (ref "C12") (pin "2") (pinfunction "2_2") (pintype "passive"))
      (node (ref "C13") (pin "2") (pinfunction "2_2") (pintype "passive"))
      (node (ref "C14") (pin "2") (pinfunction "2_2") (pintype "passive"))
      (node (ref "C15") (pin "2") (pinfunction "2_2") (pintype "passive"))
      (node (ref "C16") (pin "2") (pinfunction "2_2") (pintype "passive"))
      (node (ref "C17") (pin "2") (pinfunction "2_2") (pintype "passive"))
      (node (ref "C18") (pin "2") (pinfunction "2_2") (pintype "passive"))
      (node (ref "C19") (pin "2") (pinfunction "2_2") (pintype "passive"))
      (node (ref "C2") (pin "2") (pinfunction "2_2") (pintype "passive"))
      (node (ref "C20") (pin "2") (pinfunction "2_2") (pintype "passive"))
      (node (ref "C21") (pin "2") (pinfunction "2_2") (pintype "passive"))
      (node (ref "C22") (pin "2") (pinfunction "2_2") (pintype "passive"))
      (node (ref "C23") (pin "2") (pinfunction "2_2") (pintype "passive"))
      (node (ref "C24") (pin "2") (pinfunction "2_2") (pintype "passive"))
      (node (ref "C25") (pin "2") (pinfunction "2_2") (pintype "passive"))
      (node (ref "C26") (pin "1") (pinfunction "1_1") (pintype "passive"))
      (node (ref "C27") (pin "2") (pinfunction "2_2") (pintype "passive"))
      (node (ref "C28") (pin "1") (pinfunction "1_1") (pintype "passive"))
      (node (ref "C29") (pin "2") (pinfunction "2_2") (pintype "passive"))
      (node (ref "C3") (pin "2") (pinfunction "2_2") (pintype "passive"))
      (node (ref "C30") (pin "2") (pinfunction "2_2") (pintype "passive"))
      (node (ref "C31") (pin "2") (pinfunction "2_2") (pintype "passive"))
      (node (ref "C32") (pin "2") (pinfunction "2_2") (pintype "passive"))
      (node (ref "C33") (pin "2") (pinfunction "2_2") (pintype "passive"))
      (node (ref "C34") (pin "2") (pinfunction "2_2") (pintype "passive"))
      (node (ref "C35") (pin "2") (pinfunction "2_2") (pintype "passive"))
      (node (ref "C36") (pin "2") (pinfunction "2_2") (pintype "passive"))
      (node (ref "C37") (pin "2") (pinfunction "2_2") (pintype "passive"))
      (node (ref "C38") (pin "2") (pinfunction "2_2") (pintype "passive"))
      (node (ref "C4") (pin "2") (pinfunction "2_2") (pintype "passive"))
      (node (ref "C5") (pin "2") (pinfunction "2_2") (pintype "passive"))
      (node (ref "C6") (pin "2") (pinfunction "2_2") (pintype "passive"))
      (node (ref "C7") (pin "2") (pinfunction "2_2") (pintype "passive"))
      (node (ref "C8") (pin "2") (pinfunction "2_2") (pintype "passive"))
      (node (ref "C9") (pin "2") (pinfunction "2_2") (pintype "passive"))
      (node (ref "D5") (pin "C") (pinfunction "C_C") (pintype "passive"))
      (node (ref "D6") (pin "C") (pinfunction "C_C") (pintype "passive"))
      (node (ref "JP1") (pin "GND1") (pinfunction "GND_GND1") (pintype "bidirectional"))
      (node (ref "JP1") (pin "SHIELD1") (pinfunction "SHIELD_SHIELD1") (pintype "bidirectional"))
      (node (ref "JP1") (pin "SHIELD2") (pinfunction "SHIELD_SHIELD2") (pintype "bidirectional"))
      (node (ref "JP1") (pin "SHIELD3") (pinfunction "SHIELD_SHIELD3") (pintype "bidirectional"))
      (node (ref "JP10") (pin "1") (pinfunction "1_1") (pintype "passive"))
      (node (ref "JP11") (pin "11") (pinfunction "11_11") (pintype "passive"))
      (node (ref "JP11") (pin "12") (pinfunction "12_12") (pintype "passive"))
      (node (ref "JP12") (pin "11") (pinfunction "11_11") (pintype "passive"))
      (node (ref "JP12") (pin "12") (pinfunction "12_12") (pintype "passive"))
      (node (ref "JP13") (pin "6") (pinfunction "6_6") (pintype "bidirectional"))
      (node (ref "JP14") (pin "3") (pinfunction "3_3") (pintype "passive"))
      (node (ref "JP14") (pin "5") (pinfunction "5_5") (pintype "passive"))
      (node (ref "JP14") (pin "7") (pinfunction "7_7") (pintype "passive"))
      (node (ref "JP14") (pin "9") (pinfunction "9_9") (pintype "passive"))
      (node (ref "JP15") (pin "11") (pinfunction "11_11") (pintype "passive"))
      (node (ref "JP17") (pin "3") (pinfunction "3_3") (pintype "passive"))
      (node (ref "JP17") (pin "5") (pinfunction "5_5") (pintype "passive"))
      (node (ref "JP17") (pin "7") (pinfunction "7_7") (pintype "passive"))
      (node (ref "JP17") (pin "9") (pinfunction "9_9") (pintype "passive"))
      (node (ref "JP18") (pin "GND") (pinfunction "GND_GND") (pintype "bidirectional"))
      (node (ref "JP18") (pin "GNDBREAK") (pinfunction "GNDBREAK_GNDBREAK") (pintype "bidirectional"))
      (node (ref "JP2") (pin "GND1") (pinfunction "GND_GND1") (pintype "bidirectional"))
      (node (ref "JP2") (pin "SHIELD1") (pinfunction "SHIELD_SHIELD1") (pintype "bidirectional"))
      (node (ref "JP2") (pin "SHIELD2") (pinfunction "SHIELD_SHIELD2") (pintype "bidirectional"))
      (node (ref "JP2") (pin "SHIELD3") (pinfunction "SHIELD_SHIELD3") (pintype "bidirectional"))
      (node (ref "JP3") (pin "1") (pinfunction "1_1") (pintype "passive"))
      (node (ref "JP6") (pin "2") (pinfunction "2_2") (pintype "passive"))
      (node (ref "JP6") (pin "3") (pinfunction "3_3") (pintype "passive"))
      (node (ref "JP7") (pin "7") (pinfunction "7_7") (pintype "passive"))
      (node (ref "JP8") (pin "11") (pinfunction "11_11") (pintype "passive"))
      (node (ref "JP8") (pin "12") (pinfunction "12_12") (pintype "passive"))
      (node (ref "JP9") (pin "11") (pinfunction "11_11") (pintype "passive"))
      (node (ref "JP9") (pin "12") (pinfunction "12_12") (pintype "passive"))
      (node (ref "R5") (pin "1") (pinfunction "1_1") (pintype "passive"))
      (node (ref "R6") (pin "1") (pinfunction "1_1") (pintype "passive"))
      (node (ref "S1") (pin "3") (pinfunction "2_3") (pintype "passive"))
      (node (ref "S2") (pin "3") (pinfunction "2_3") (pintype "passive"))
      (node (ref "S5") (pin "3") (pinfunction "2_3") (pintype "passive"))
      (node (ref "S6") (pin "3") (pinfunction "2_3") (pintype "passive"))
      (node (ref "U1") (pin "10") (pinfunction "VSSB_10") (pintype "bidirectional"))
      (node (ref "U1") (pin "12") (pinfunction "VBOOST_12") (pintype "bidirectional"))
      (node (ref "U1") (pin "13") (pinfunction "VBAT_13") (pintype "bidirectional"))
      (node (ref "U1") (pin "14") (pinfunction "VSSD0_14") (pintype "bidirectional"))
      (node (ref "U1") (pin "38") (pinfunction "VSSD1_38") (pintype "bidirectional"))
      (node (ref "U1") (pin "64") (pinfunction "VSSA_64") (pintype "bidirectional"))
      (node (ref "U1") (pin "66") (pinfunction "VSSD2_66") (pintype "bidirectional"))
      (node (ref "U1") (pin "87") (pinfunction "VSSD3_87") (pintype "bidirectional"))
      (node (ref "U2") (pin "2") (pinfunction "GND_2") (pintype "input"))
      (node (ref "U3") (pin "2") (pinfunction "GND_2") (pintype "input"))
      (node (ref "U7") (pin "25") (pinfunction "VSSD1_25") (pintype "bidirectional"))
      (node (ref "U7") (pin "43") (pinfunction "VSSA_43") (pintype "bidirectional"))
      (node (ref "U7") (pin "45") (pinfunction "VSSD2_45") (pintype "bidirectional"))
      (node (ref "U7") (pin "5") (pinfunction "VSSB_5") (pintype "bidirectional"))
      (node (ref "U7") (pin "54") (pinfunction "P0[5]_54") (pintype "bidirectional"))
      (node (ref "U7") (pin "56") (pinfunction "P0[7]_56") (pintype "bidirectional"))
      (node (ref "U7") (pin "58") (pinfunction "VSSD3_58") (pintype "bidirectional"))
      (node (ref "U7") (pin "69") (pinfunction "VSSD0_69") (pintype "bidirectional"))
      (node (ref "U7") (pin "7") (pinfunction "VBOOST_7") (pintype "bidirectional"))
      (node (ref "U7") (pin "8") (pinfunction "VBAT_8") (pintype "bidirectional"))
      (node (ref "U7") (pin "9") (pinfunction "VSSD0_9") (pintype "bidirectional"))
    )
    (net (code "47") (name "Net-(C34-Pad1)") (class "Default")
      (node (ref "C34") (pin "1") (pinfunction "1_1") (pintype "passive"))
      (node (ref "SJ5") (pin "2") (pinfunction "2_2") (pintype "passive"))
    )
    (net (code "48") (name "Net-(C35-Pad1)") (class "Default")
      (node (ref "C35") (pin "1") (pinfunction "1_1") (pintype "passive"))
      (node (ref "SJ4") (pin "2") (pinfunction "2_2") (pintype "passive"))
    )
    (net (code "49") (name "Net-(C36-Pad1)") (class "Default")
      (node (ref "C36") (pin "1") (pinfunction "1_1") (pintype "passive"))
      (node (ref "SJ3") (pin "2") (pinfunction "2_2") (pintype "passive"))
    )
    (net (code "50") (name "Net-(D1-PadC)") (class "Default")
      (node (ref "D1") (pin "C") (pinfunction "C_C") (pintype "passive"))
      (node (ref "D2") (pin "C") (pinfunction "C_C") (pintype "passive"))
      (node (ref "D3") (pin "C") (pinfunction "C_C") (pintype "passive"))
      (node (ref "SJ1") (pin "1") (pinfunction "1_1") (pintype "passive"))
    )
    (net (code "51") (name "Net-(D3-PadA)") (class "Default")
      (node (ref "D3") (pin "A") (pinfunction "A_A") (pintype "passive"))
      (node (ref "JP18") (pin "PWR") (pinfunction "PWR_PWR") (pintype "bidirectional"))
    )
    (net (code "52") (name "Net-(D4-PadA)") (class "Default")
      (node (ref "D4") (pin "A") (pinfunction "A_A") (pintype "passive"))
      (node (ref "JP3") (pin "2") (pinfunction "2_2") (pintype "passive"))
      (node (ref "SJ2") (pin "1") (pinfunction "1_1") (pintype "passive"))
    )
    (net (code "53") (name "Net-(D5-PadA)") (class "Default")
      (node (ref "D5") (pin "A") (pinfunction "A_A") (pintype "passive"))
      (node (ref "R21") (pin "2") (pinfunction "2_2") (pintype "passive"))
    )
    (net (code "54") (name "Net-(D6-PadA)") (class "Default")
      (node (ref "D6") (pin "A") (pinfunction "A_A") (pintype "passive"))
      (node (ref "R20") (pin "2") (pinfunction "2_2") (pintype "passive"))
    )
    (net (code "55") (name "Net-(U1E-P15[6])") (class "Default")
      (node (ref "R16") (pin "1") (pinfunction "1_1") (pintype "passive"))
      (node (ref "U1") (pin "35") (pinfunction "P15[6]_35") (pintype "bidirectional"))
    )
    (net (code "56") (name "Net-(U1E-P15[7])") (class "Default")
      (node (ref "R17") (pin "1") (pinfunction "1_1") (pintype "passive"))
      (node (ref "U1") (pin "36") (pinfunction "P15[7]_36") (pintype "bidirectional"))
    )
    (net (code "57") (name "Net-(U1E-VCCA)") (class "Default")
      (node (ref "C1") (pin "1") (pinfunction "1_1") (pintype "passive"))
      (node (ref "U1") (pin "63") (pinfunction "VCCA_63") (pintype "bidirectional"))
    )
    (net (code "58") (name "Net-(U1E-VCCD0)") (class "Default")
      (node (ref "C7") (pin "1") (pinfunction "1_1") (pintype "passive"))
      (node (ref "U1") (pin "39") (pinfunction "VCCD0_39") (pintype "bidirectional"))
      (node (ref "U1") (pin "86") (pinfunction "VCCD1_86") (pintype "bidirectional"))
    )
    (net (code "59") (name "Net-(U2-BP)") (class "Default")
      (node (ref "C10") (pin "1") (pinfunction "1_1") (pintype "passive"))
      (node (ref "U2") (pin "4") (pinfunction "BP_4") (pintype "input"))
    )
    (net (code "60") (name "Net-(U3-BP)") (class "Default")
      (node (ref "C8") (pin "1") (pinfunction "1_1") (pintype "passive"))
      (node (ref "U3") (pin "4") (pinfunction "BP_4") (pintype "input"))
    )
    (net (code "61") (name "Net-(U4A-S)") (class "Default")
      (node (ref "R7") (pin "1") (pinfunction "1_1") (pintype "passive"))
      (node (ref "U4") (pin "S1") (pinfunction "S_S1") (pintype "passive"))
    )
    (net (code "62") (name "Net-(U4B-S)") (class "Default")
      (node (ref "R8") (pin "1") (pinfunction "1_1") (pintype "passive"))
      (node (ref "U4") (pin "S2") (pinfunction "S_S2") (pintype "passive"))
    )
    (net (code "63") (name "Net-(U7E-P15[6])") (class "Default")
      (node (ref "R18") (pin "1") (pinfunction "1_1") (pintype "passive"))
      (node (ref "U7") (pin "22") (pinfunction "P15[6]_22") (pintype "bidirectional"))
    )
    (net (code "64") (name "Net-(U7E-P15[7])") (class "Default")
      (node (ref "R19") (pin "1") (pinfunction "1_1") (pintype "passive"))
      (node (ref "U7") (pin "23") (pinfunction "P15[7]_23") (pintype "bidirectional"))
    )
    (net (code "65") (name "Net-(U7E-VCCA)") (class "Default")
      (node (ref "C17") (pin "1") (pinfunction "1_1") (pintype "passive"))
      (node (ref "U7") (pin "42") (pinfunction "VCCA_42") (pintype "bidirectional"))
    )
    (net (code "66") (name "Net-(U7E-VCCD0)") (class "Default")
      (node (ref "C16") (pin "1") (pinfunction "1_1") (pintype "passive"))
      (node (ref "U7") (pin "26") (pinfunction "VCCD0_26") (pintype "bidirectional"))
      (node (ref "U7") (pin "57") (pinfunction "VCCD1_57") (pintype "bidirectional"))
    )
    (net (code "67") (name "P0.0") (class "Default")
      (node (ref "JP8") (pin "1") (pinfunction "1_1") (pintype "passive"))
      (node (ref "U1") (pin "71") (pinfunction "P0[0]_71") (pintype "bidirectional"))
    )
    (net (code "68") (name "P0.1") (class "Default")
      (node (ref "JP8") (pin "2") (pinfunction "2_2") (pintype "passive"))
      (node (ref "U1") (pin "72") (pinfunction "P0[1]_72") (pintype "bidirectional"))
    )
    (net (code "69") (name "P0.2") (class "Default")
      (node (ref "JP8") (pin "3") (pinfunction "3_3") (pintype "passive"))
      (node (ref "SJ3") (pin "1") (pinfunction "1_1") (pintype "passive"))
      (node (ref "U1") (pin "73") (pinfunction "P0[2]_73") (pintype "bidirectional"))
    )
    (net (code "70") (name "P0.3") (class "Default")
      (node (ref "JP8") (pin "4") (pinfunction "4_4") (pintype "passive"))
      (node (ref "SJ4") (pin "1") (pinfunction "1_1") (pintype "passive"))
      (node (ref "U1") (pin "74") (pinfunction "P0[3]_74") (pintype "bidirectional"))
    )
    (net (code "71") (name "P0.4") (class "Default")
      (node (ref "JP8") (pin "5") (pinfunction "5_5") (pintype "passive"))
      (node (ref "SJ5") (pin "1") (pinfunction "1_1") (pintype "passive"))
      (node (ref "U1") (pin "76") (pinfunction "P0[4]_76") (pintype "bidirectional"))
    )
    (net (code "72") (name "P0.5") (class "Default")
      (node (ref "JP8") (pin "6") (pinfunction "6_6") (pintype "passive"))
      (node (ref "U1") (pin "77") (pinfunction "P0[5]_77") (pintype "bidirectional"))
    )
    (net (code "73") (name "P0.6") (class "Default")
      (node (ref "JP8") (pin "7") (pinfunction "7_7") (pintype "passive"))
      (node (ref "U1") (pin "78") (pinfunction "P0[6]_78") (pintype "bidirectional"))
    )
    (net (code "74") (name "P0.7") (class "Default")
      (node (ref "JP8") (pin "8") (pinfunction "8_8") (pintype "passive"))
      (node (ref "U1") (pin "79") (pinfunction "P0[7]_79") (pintype "bidirectional"))
    )
    (net (code "75") (name "P1.0") (class "Default")
      (node (ref "JP17") (pin "2") (pinfunction "2_2") (pintype "passive"))
      (node (ref "U1") (pin "20") (pinfunction "P1[0]_20") (pintype "bidirectional"))
      (node (ref "U7") (pin "46") (pinfunction "P12[2]_46") (pintype "bidirectional"))
    )
    (net (code "76") (name "P1.1") (class "Default")
      (node (ref "JP17") (pin "4") (pinfunction "4_4") (pintype "passive"))
      (node (ref "U1") (pin "21") (pinfunction "P1[1]_21") (pintype "bidirectional"))
      (node (ref "U7") (pin "47") (pinfunction "P12[3]_47") (pintype "bidirectional"))
    )
    (net (code "77") (name "P1.2") (class "Default")
      (node (ref "S6") (pin "1") (pinfunction "1_1") (pintype "passive"))
      (node (ref "U1") (pin "22") (pinfunction "P1[2]_22") (pintype "bidirectional"))
    )
    (net (code "78") (name "P1.3") (class "Default")
      (node (ref "JP17") (pin "6") (pinfunction "6_6") (pintype "passive"))
      (node (ref "U1") (pin "23") (pinfunction "P1[3]_23") (pintype "bidirectional"))
    )
    (net (code "79") (name "P1.4") (class "Default")
      (node (ref "JP17") (pin "8") (pinfunction "8_8") (pintype "passive"))
      (node (ref "U1") (pin "24") (pinfunction "P1[4]_24") (pintype "bidirectional"))
    )
    (net (code "80") (name "P3.0") (class "Default")
      (node (ref "JP12") (pin "1") (pinfunction "1_1") (pintype "passive"))
      (node (ref "U1") (pin "44") (pinfunction "P3[0]_44") (pintype "bidirectional"))
    )
    (net (code "81") (name "P3.1") (class "Default")
      (node (ref "JP12") (pin "2") (pinfunction "2_2") (pintype "passive"))
      (node (ref "U1") (pin "45") (pinfunction "P3[1]_45") (pintype "bidirectional"))
    )
    (net (code "82") (name "P3.2") (class "Default")
      (node (ref "JP12") (pin "3") (pinfunction "3_3") (pintype "passive"))
      (node (ref "U1") (pin "46") (pinfunction "P3[2]_46") (pintype "bidirectional"))
    )
    (net (code "83") (name "P3.3") (class "Default")
      (node (ref "JP12") (pin "4") (pinfunction "4_4") (pintype "passive"))
      (node (ref "U1") (pin "47") (pinfunction "P3[3]_47") (pintype "bidirectional"))
    )
    (net (code "84") (name "P3.4") (class "Default")
      (node (ref "JP12") (pin "5") (pinfunction "5_5") (pintype "passive"))
      (node (ref "U1") (pin "48") (pinfunction "P3[4]_48") (pintype "bidirectional"))
    )
    (net (code "85") (name "P3.5") (class "Default")
      (node (ref "JP12") (pin "6") (pinfunction "6_6") (pintype "passive"))
      (node (ref "U1") (pin "49") (pinfunction "P3[5]_49") (pintype "bidirectional"))
    )
    (net (code "86") (name "P3.6") (class "Default")
      (node (ref "JP12") (pin "7") (pinfunction "7_7") (pintype "passive"))
      (node (ref "U1") (pin "51") (pinfunction "P3[6]_51") (pintype "bidirectional"))
    )
    (net (code "87") (name "P3.7") (class "Default")
      (node (ref "JP12") (pin "8") (pinfunction "8_8") (pintype "passive"))
      (node (ref "U1") (pin "52") (pinfunction "P3[7]_52") (pintype "bidirectional"))
    )
    (net (code "88") (name "P4.0") (class "Default")
      (node (ref "JP9") (pin "2") (pinfunction "2_2") (pintype "passive"))
      (node (ref "U1") (pin "69") (pinfunction "P4[0]_69") (pintype "bidirectional"))
    )
    (net (code "89") (name "P4.1") (class "Default")
      (node (ref "JP9") (pin "1") (pinfunction "1_1") (pintype "passive"))
      (node (ref "U1") (pin "70") (pinfunction "P4[1]_70") (pintype "bidirectional"))
    )
    (net (code "90") (name "P4.2") (class "Default")
      (node (ref "JP9") (pin "4") (pinfunction "4_4") (pintype "passive"))
      (node (ref "U1") (pin "80") (pinfunction "P4[2]_80") (pintype "bidirectional"))
    )
    (net (code "91") (name "P4.3") (class "Default")
      (node (ref "JP9") (pin "3") (pinfunction "3_3") (pintype "passive"))
      (node (ref "U1") (pin "81") (pinfunction "P4[3]_81") (pintype "bidirectional"))
    )
    (net (code "92") (name "P4.4") (class "Default")
      (node (ref "JP9") (pin "6") (pinfunction "6_6") (pintype "passive"))
      (node (ref "U1") (pin "82") (pinfunction "P4[4]_82") (pintype "bidirectional"))
    )
    (net (code "93") (name "P4.5") (class "Default")
      (node (ref "JP9") (pin "5") (pinfunction "5_5") (pintype "passive"))
      (node (ref "U1") (pin "83") (pinfunction "P4[5]_83") (pintype "bidirectional"))
    )
    (net (code "94") (name "P4.6") (class "Default")
      (node (ref "JP9") (pin "8") (pinfunction "8_8") (pintype "passive"))
      (node (ref "U1") (pin "84") (pinfunction "P4[6]_84") (pintype "bidirectional"))
    )
    (net (code "95") (name "P4.7") (class "Default")
      (node (ref "JP9") (pin "7") (pinfunction "7_7") (pintype "passive"))
      (node (ref "U1") (pin "85") (pinfunction "P4[7]_85") (pintype "bidirectional"))
    )
    (net (code "96") (name "P5.0") (class "Default")
      (node (ref "JP11") (pin "2") (pinfunction "2_2") (pintype "passive"))
      (node (ref "U1") (pin "16") (pinfunction "P5[0]_16") (pintype "bidirectional"))
    )
    (net (code "97") (name "P5.1") (class "Default")
      (node (ref "JP11") (pin "1") (pinfunction "1_1") (pintype "passive"))
      (node (ref "U1") (pin "17") (pinfunction "P5[1]_17") (pintype "bidirectional"))
    )
    (net (code "98") (name "P5.2") (class "Default")
      (node (ref "JP11") (pin "4") (pinfunction "4_4") (pintype "passive"))
      (node (ref "U1") (pin "18") (pinfunction "P5[2]_18") (pintype "bidirectional"))
    )
    (net (code "99") (name "P5.3") (class "Default")
      (node (ref "JP11") (pin "3") (pinfunction "3_3") (pintype "passive"))
      (node (ref "U1") (pin "19") (pinfunction "P5[3]_19") (pintype "bidirectional"))
    )
    (net (code "100") (name "P5.4") (class "Default")
      (node (ref "JP11") (pin "6") (pinfunction "6_6") (pintype "passive"))
      (node (ref "U1") (pin "31") (pinfunction "P5[4]_31") (pintype "bidirectional"))
    )
    (net (code "101") (name "P5.5") (class "Default")
      (node (ref "JP11") (pin "5") (pinfunction "5_5") (pintype "passive"))
      (node (ref "U1") (pin "32") (pinfunction "P5[5]_32") (pintype "bidirectional"))
    )
    (net (code "102") (name "P5.6") (class "Default")
      (node (ref "JP11") (pin "8") (pinfunction "8_8") (pintype "passive"))
      (node (ref "U1") (pin "33") (pinfunction "P5[6]_33") (pintype "bidirectional"))
    )
    (net (code "103") (name "P5.7") (class "Default")
      (node (ref "JP11") (pin "7") (pinfunction "7_7") (pintype "passive"))
      (node (ref "U1") (pin "34") (pinfunction "P5[7]_34") (pintype "bidirectional"))
    )
    (net (code "104") (name "P12.0") (class "Default")
      (node (ref "JP10") (pin "3") (pinfunction "3_3") (pintype "passive"))
      (node (ref "U1") (pin "53") (pinfunction "P12[0]_53") (pintype "bidirectional"))
    )
    (net (code "105") (name "P12.1") (class "Default")
      (node (ref "JP10") (pin "4") (pinfunction "4_4") (pintype "passive"))
      (node (ref "U1") (pin "54") (pinfunction "P12[1]_54") (pintype "bidirectional"))
    )
    (net (code "106") (name "P12.2") (class "Default")
      (node (ref "JP10") (pin "5") (pinfunction "5_5") (pintype "passive"))
      (node (ref "U1") (pin "67") (pinfunction "P12[2]_67") (pintype "bidirectional"))
    )
    (net (code "107") (name "P12.3") (class "Default")
      (node (ref "JP10") (pin "6") (pinfunction "6_6") (pintype "passive"))
      (node (ref "U1") (pin "68") (pinfunction "P12[3]_68") (pintype "bidirectional"))
    )
    (net (code "108") (name "P12.6") (class "Default")
      (node (ref "JP10") (pin "7") (pinfunction "7_7") (pintype "passive"))
      (node (ref "U1") (pin "29") (pinfunction "P12[6]_29") (pintype "bidirectional"))
    )
    (net (code "109") (name "P12.7") (class "Default")
      (node (ref "JP10") (pin "8") (pinfunction "8_8") (pintype "passive"))
      (node (ref "U1") (pin "30") (pinfunction "P12[7]_30") (pintype "bidirectional"))
    )
    (net (code "110") (name "P15.0") (class "Default")
      (node (ref "C14") (pin "1") (pinfunction "1_1") (pintype "passive"))
      (node (ref "U1") (pin "42") (pinfunction "P15[0]_42") (pintype "bidirectional"))
      (node (ref "Y2") (pin "1") (pinfunction "1_1") (pintype "passive"))
    )
    (net (code "111") (name "P15.1") (class "Default")
      (node (ref "C12") (pin "1") (pinfunction "1_1") (pintype "passive"))
      (node (ref "U1") (pin "43") (pinfunction "P15[1]_43") (pintype "bidirectional"))
      (node (ref "Y2") (pin "2") (pinfunction "2_2") (pintype "passive"))
    )
    (net (code "112") (name "P15.2") (class "Default")
      (node (ref "C18") (pin "1") (pinfunction "1_1") (pintype "passive"))
      (node (ref "U1") (pin "55") (pinfunction "P15[2]_55") (pintype "bidirectional"))
      (node (ref "Y1") (pin "2") (pinfunction "2_2") (pintype "passive"))
    )
    (net (code "113") (name "P15.3") (class "Default")
      (node (ref "C24") (pin "1") (pinfunction "1_1") (pintype "passive"))
      (node (ref "U1") (pin "56") (pinfunction "P15[3]_56") (pintype "bidirectional"))
      (node (ref "Y1") (pin "1") (pinfunction "1_1") (pintype "passive"))
    )
    (net (code "114") (name "PSOC_D+_BUS") (class "Default")
      (node (ref "JP1") (pin "D+1") (pinfunction "D+_D+1") (pintype "bidirectional"))
      (node (ref "R16") (pin "2") (pinfunction "2_2") (pintype "passive"))
    )
    (net (code "115") (name "PSOC_D-_BUS") (class "Default")
      (node (ref "JP1") (pin "D-1") (pinfunction "D-_D-1") (pintype "bidirectional"))
      (node (ref "R17") (pin "2") (pinfunction "2_2") (pintype "passive"))
    )
    (net (code "116") (name "VDDIO") (class "Default")
      (node (ref "C13") (pin "1") (pinfunction "1_1") (pintype "passive"))
      (node (ref "C15") (pin "1") (pinfunction "1_1") (pintype "passive"))
      (node (ref "C25") (pin "1") (pinfunction "1_1") (pintype "passive"))
      (node (ref "C27") (pin "1") (pinfunction "1_1") (pintype "passive"))
      (node (ref "C29") (pin "1") (pinfunction "1_1") (pintype "passive"))
      (node (ref "C31") (pin "1") (pinfunction "1_1") (pintype "passive"))
      (node (ref "C9") (pin "1") (pinfunction "1_1") (pintype "passive"))
      (node (ref "JP10") (pin "2") (pinfunction "2_2") (pintype "passive"))
      (node (ref "JP11") (pin "10") (pinfunction "10_10") (pintype "passive"))
      (node (ref "JP11") (pin "9") (pinfunction "9_9") (pintype "passive"))
      (node (ref "JP12") (pin "10") (pinfunction "10_10") (pintype "passive"))
      (node (ref "JP12") (pin "9") (pinfunction "9_9") (pintype "passive"))
      (node (ref "JP14") (pin "1") (pinfunction "1_1") (pintype "passive"))
      (node (ref "JP15") (pin "1") (pinfunction "1_1") (pintype "passive"))
      (node (ref "JP17") (pin "1") (pinfunction "1_1") (pintype "passive"))
      (node (ref "JP8") (pin "10") (pinfunction "10_10") (pintype "passive"))
      (node (ref "JP8") (pin "9") (pinfunction "9_9") (pintype "passive"))
      (node (ref "JP9") (pin "10") (pinfunction "10_10") (pintype "passive"))
      (node (ref "JP9") (pin "9") (pinfunction "9_9") (pintype "passive"))
      (node (ref "R7") (pin "2") (pinfunction "2_2") (pintype "passive"))
      (node (ref "R8") (pin "2") (pinfunction "2_2") (pintype "passive"))
      (node (ref "S4") (pin "2") (pinfunction "P_2") (pintype "passive"))
      (node (ref "U1") (pin "26") (pinfunction "VDDIO1_26") (pintype "bidirectional"))
      (node (ref "U1") (pin "50") (pinfunction "VDDIO3_50") (pintype "bidirectional"))
      (node (ref "U1") (pin "75") (pinfunction "VDDIO0_75") (pintype "bidirectional"))
      (node (ref "U7") (pin "17") (pinfunction "VDDIO1_17") (pintype "bidirectional"))
      (node (ref "U7") (pin "35") (pinfunction "VDDIO3_35") (pintype "bidirectional"))
      (node (ref "U7") (pin "52") (pinfunction "VDDIO0_52") (pintype "bidirectional"))
      (node (ref "U7") (pin "67") (pinfunction "VDDIO2_67") (pintype "bidirectional"))
    )
    (net (code "117") (name "VDDIO_ARDUINO") (class "Default")
      (node (ref "C11") (pin "1") (pinfunction "1_1") (pintype "passive"))
      (node (ref "JP13") (pin "2") (pinfunction "2_2") (pintype "bidirectional"))
      (node (ref "JP6") (pin "7") (pinfunction "7_7") (pintype "passive"))
      (node (ref "S3") (pin "2") (pinfunction "P_2") (pintype "passive"))
      (node (ref "U1") (pin "100") (pinfunction "VDDIO2_100") (pintype "bidirectional"))
    )
    (net (code "118") (name "V_BUS_DEBUG") (class "Default")
      (node (ref "R4") (pin "2") (pinfunction "2_2") (pintype "passive"))
      (node (ref "R5") (pin "2") (pinfunction "2_2") (pintype "passive"))
      (node (ref "U7") (pin "18") (pinfunction "P1[6]_18") (pintype "bidirectional"))
    )
    (net (code "119") (name "V_BUS_HOST") (class "Default")
      (node (ref "R3") (pin "2") (pinfunction "2_2") (pintype "passive"))
      (node (ref "R6") (pin "2") (pinfunction "2_2") (pintype "passive"))
      (node (ref "U1") (pin "27") (pinfunction "P1[6]_27") (pintype "bidirectional"))
    )
    (net (code "120") (name "V_DEBUG") (class "Default")
      (node (ref "D2") (pin "A") (pinfunction "A_A") (pintype "passive"))
      (node (ref "JP2") (pin "VBUS1") (pinfunction "VCC_VBUS1") (pintype "bidirectional"))
      (node (ref "R4") (pin "1") (pinfunction "1_1") (pintype "passive"))
    )
    (net (code "121") (name "V_HOST") (class "Default")
      (node (ref "D1") (pin "A") (pinfunction "A_A") (pintype "passive"))
      (node (ref "JP1") (pin "VBUS1") (pinfunction "VCC_VBUS1") (pintype "bidirectional"))
      (node (ref "R3") (pin "1") (pinfunction "1_1") (pintype "passive"))
    )
    (net (code "122") (name "V_IN") (class "Default")
      (node (ref "D4") (pin "C") (pinfunction "C_C") (pintype "passive"))
      (node (ref "JP6") (pin "1") (pinfunction "1_1") (pintype "passive"))
      (node (ref "SJ1") (pin "2") (pinfunction "2_2") (pintype "passive"))
      (node (ref "SJ2") (pin "2") (pinfunction "2_2") (pintype "passive"))
      (node (ref "U2") (pin "1") (pinfunction "IN_1") (pintype "input"))
      (node (ref "U2") (pin "3") (pinfunction "EN_3") (pintype "input"))
      (node (ref "U3") (pin "1") (pinfunction "IN_1") (pintype "input"))
      (node (ref "U3") (pin "3") (pinfunction "EN_3") (pintype "input"))
    )
    (net (code "123") (name "unconnected-(JP1-ID-PadID1)") (class "Default")
      (node (ref "JP1") (pin "ID1") (pinfunction "ID_ID1") (pintype "bidirectional"))
    )
    (net (code "124") (name "unconnected-(JP2-ID-PadID1)") (class "Default")
      (node (ref "JP2") (pin "ID1") (pinfunction "ID_ID1") (pintype "bidirectional"))
    )
    (net (code "125") (name "unconnected-(JP6-Pad8)") (class "Default")
      (node (ref "JP6") (pin "8") (pinfunction "8_8") (pintype "passive"))
    )
    (net (code "126") (name "unconnected-(JP7-Pad8)") (class "Default")
      (node (ref "JP7") (pin "8") (pinfunction "8_8") (pintype "passive"))
    )
    (net (code "127") (name "unconnected-(U1B-P1[5]-Pad25)") (class "Default")
      (node (ref "U1") (pin "25") (pinfunction "P1[5]_25") (pintype "bidirectional"))
    )
    (net (code "128") (name "unconnected-(U1B-P1[7]-Pad28)") (class "Default")
      (node (ref "U1") (pin "28") (pinfunction "P1[7]_28") (pintype "bidirectional"))
    )
    (net (code "129") (name "unconnected-(U1E-IND-Pad11)") (class "Default")
      (node (ref "U1") (pin "11") (pinfunction "IND_11") (pintype "bidirectional"))
    )
    (net (code "130") (name "unconnected-(U7A-P0[6]-Pad55)") (class "Default")
      (node (ref "U7") (pin "55") (pinfunction "P0[6]_55") (pintype "bidirectional"))
    )
    (net (code "131") (name "unconnected-(U7B-P1[5]-Pad16)") (class "Default")
      (node (ref "U7") (pin "16") (pinfunction "P1[5]_16") (pintype "bidirectional"))
    )
    (net (code "132") (name "unconnected-(U7B-P1[7]-Pad19)") (class "Default")
      (node (ref "U7") (pin "19") (pinfunction "P1[7]_19") (pintype "bidirectional"))
    )
    (net (code "133") (name "unconnected-(U7C-P2[0]-Pad62)") (class "Default")
      (node (ref "U7") (pin "62") (pinfunction "P2[0]_62") (pintype "bidirectional"))
    )
    (net (code "134") (name "unconnected-(U7C-P2[1]-Pad63)") (class "Default")
      (node (ref "U7") (pin "63") (pinfunction "P2[1]_63") (pintype "bidirectional"))
    )
    (net (code "135") (name "unconnected-(U7C-P2[3]-Pad65)") (class "Default")
      (node (ref "U7") (pin "65") (pinfunction "P2[3]_65") (pintype "bidirectional"))
    )
    (net (code "136") (name "unconnected-(U7C-P2[4]-Pad66)") (class "Default")
      (node (ref "U7") (pin "66") (pinfunction "P2[4]_66") (pintype "bidirectional"))
    )
    (net (code "137") (name "unconnected-(U7C-P2[5]-Pad68)") (class "Default")
      (node (ref "U7") (pin "68") (pinfunction "P2[5]_68") (pintype "bidirectional"))
    )
    (net (code "138") (name "unconnected-(U7C-P12[5]-Pad4)") (class "Default")
      (node (ref "U7") (pin "4") (pinfunction "P12[5]_4") (pintype "bidirectional"))
    )
    (net (code "139") (name "unconnected-(U7C-P15[4]-Pad60)") (class "Default")
      (node (ref "U7") (pin "60") (pinfunction "P15[4]_60") (pintype "bidirectional"))
    )
    (net (code "140") (name "unconnected-(U7C-P15[5]-Pad61)") (class "Default")
      (node (ref "U7") (pin "61") (pinfunction "P15[5]_61") (pintype "bidirectional"))
    )
    (net (code "141") (name "unconnected-(U7D-P3[2]-Pad31)") (class "Default")
      (node (ref "U7") (pin "31") (pinfunction "P3[2]_31") (pintype "bidirectional"))
    )
    (net (code "142") (name "unconnected-(U7D-P3[3]-Pad32)") (class "Default")
      (node (ref "U7") (pin "32") (pinfunction "P3[3]_32") (pintype "bidirectional"))
    )
    (net (code "143") (name "unconnected-(U7D-P15[0]-Pad27)") (class "Default")
      (node (ref "U7") (pin "27") (pinfunction "P15[0]_27") (pintype "bidirectional"))
    )
    (net (code "144") (name "unconnected-(U7D-P15[1]-Pad28)") (class "Default")
      (node (ref "U7") (pin "28") (pinfunction "P15[1]_28") (pintype "bidirectional"))
    )
    (net (code "145") (name "unconnected-(U7D-P15[2]-Pad40)") (class "Default")
      (node (ref "U7") (pin "40") (pinfunction "P15[2]_40") (pintype "bidirectional"))
    )
    (net (code "146") (name "unconnected-(U7D-P15[3]-Pad41)") (class "Default")
      (node (ref "U7") (pin "41") (pinfunction "P15[3]_41") (pintype "bidirectional"))
    )
    (net (code "147") (name "unconnected-(U7E-IND-Pad6)") (class "Default")
      (node (ref "U7") (pin "6") (pinfunction "IND_6") (pintype "bidirectional"))
    )
    (net (code "148") (name "~{DEBUG_P2.6_SCL_PU_EN}") (class "Default")
      (node (ref "U4") (pin "G2") (pinfunction "G_G2") (pintype "passive"))
      (node (ref "U7") (pin "1") (pinfunction "P2[6]_1") (pintype "bidirectional"))
    )
    (net (code "149") (name "~{DEBUG_P2.7_SDA_PU_EN}") (class "Default")
      (node (ref "U4") (pin "G1") (pinfunction "G_G1") (pintype "passive"))
      (node (ref "U7") (pin "2") (pinfunction "P2[7]_2") (pintype "bidirectional"))
    )
    (net (code "150") (name "~{DEBUG_RESET}") (class "Default")
      (node (ref "C38") (pin "1") (pinfunction "1_1") (pintype "passive"))
      (node (ref "JP14") (pin "10") (pinfunction "10_10") (pintype "passive"))
      (node (ref "R2") (pin "1") (pinfunction "1_1") (pintype "passive"))
      (node (ref "S1") (pin "1") (pinfunction "1_1") (pintype "passive"))
      (node (ref "U7") (pin "10") (pinfunction "~{XRES}_10") (pintype "bidirectional"))
    )
    (net (code "151") (name "~{RESET}") (class "Default")
      (node (ref "C37") (pin "1") (pinfunction "1_1") (pintype "passive"))
      (node (ref "JP13") (pin "5") (pinfunction "5_5") (pintype "bidirectional"))
      (node (ref "JP17") (pin "10") (pinfunction "10_10") (pintype "passive"))
      (node (ref "JP6") (pin "6") (pinfunction "6_6") (pintype "passive"))
      (node (ref "R1") (pin "1") (pinfunction "1_1") (pintype "passive"))
      (node (ref "S2") (pin "1") (pinfunction "1_1") (pintype "passive"))
      (node (ref "U1") (pin "15") (pinfunction "~{XRES}_15") (pintype "bidirectional"))
      (node (ref "U7") (pin "3") (pinfunction "P12[4]_3") (pintype "bidirectional"))
    )
  )
)
